# channel_1.net
KiCad netlist of a schematic drawn in Altium Designer
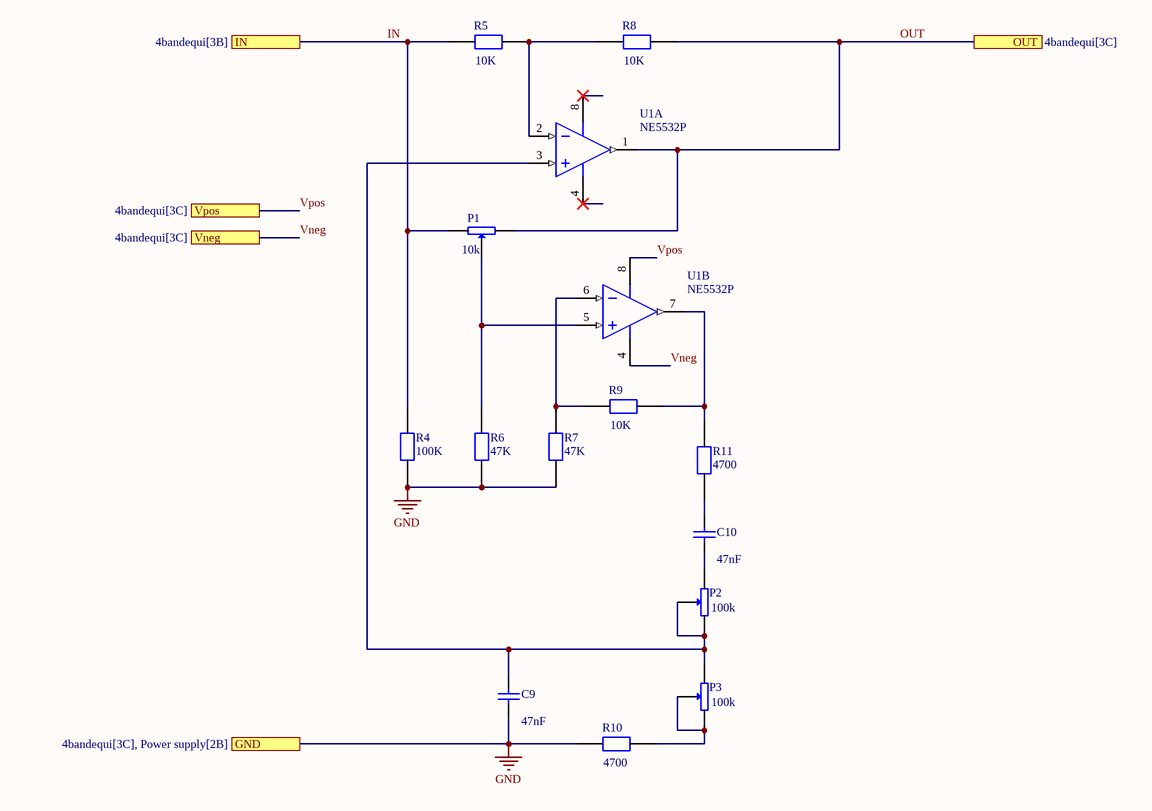
[diagram p0: channel 1.SchDoc]

(export (version "E")
  (design (tool "Eeschema 10.0.6"))
  (components
    (comp (ref "C9")
      (value "47nF")
      (footprint "Capacitor")
      (description "Capacitor")
      (fields (field (name "Comment") "Cap") (field (name "PUBLISHER") "Altium Limited"))
      (libsource (lib "Miscellaneous Devices") (part "Cap"))
    )
    (comp (ref "C10")
      (value "47nF")
      (footprint "Capacitor")
      (description "Capacitor")
      (fields (field (name "Comment") "Cap") (field (name "PUBLISHER") "Altium Limited"))
      (libsource (lib "Miscellaneous Devices") (part "Cap"))
    )
    (comp (ref "P1")
      (value "10k")
      (footprint "header 3")
      (fields (field (name "Comment") "potentiometer"))
      (libsource (lib "4bandequi") (part "potentiometer"))
    )
    (comp (ref "P2")
      (value "100k")
      (footprint "header 3")
      (fields (field (name "Comment") "potentiometer"))
      (libsource (lib "4bandequi") (part "potentiometer"))
    )
    (comp (ref "P3")
      (value "100k")
      (footprint "header 3")
      (fields (field (name "Comment") "potentiometer"))
      (libsource (lib "4bandequi") (part "potentiometer"))
    )
    (comp (ref "R4")
      (value "100K")
      (footprint "resistor")
      (description "resistor")
      (fields (field (name "Comment") "Resistor_Axial"))
      (libsource (lib "4bandequi") (part "Resistor_Axial"))
    )
    (comp (ref "R5")
      (value "10K")
      (footprint "resistor")
      (description "resistor")
      (fields (field (name "Comment") "Resistor_Axial"))
      (libsource (lib "4bandequi") (part "Resistor_Axial"))
    )
    (comp (ref "R6")
      (value "47K")
      (footprint "resistor")
      (description "resistor")
      (fields (field (name "Comment") "Resistor_Axial"))
      (libsource (lib "4bandequi") (part "Resistor_Axial"))
    )
    (comp (ref "R7")
      (value "47K")
      (footprint "resistor")
      (description "resistor")
      (fields (field (name "Comment") "Resistor_Axial"))
      (libsource (lib "4bandequi") (part "Resistor_Axial"))
    )
    (comp (ref "R8")
      (value "10K")
      (footprint "resistor")
      (description "resistor")
      (fields (field (name "Comment") "Resistor_Axial"))
      (libsource (lib "4bandequi") (part "Resistor_Axial"))
    )
    (comp (ref "R9")
      (value "10K")
      (footprint "resistor")
      (description "resistor")
      (fields (field (name "Comment") "Resistor_Axial"))
      (libsource (lib "4bandequi") (part "Resistor_Axial"))
    )
    (comp (ref "R10")
      (value "4700")
      (footprint "resistor")
      (description "resistor")
      (fields (field (name "Comment") "Resistor_Axial"))
      (libsource (lib "4bandequi") (part "Resistor_Axial"))
    )
    (comp (ref "R11")
      (value "4700")
      (footprint "resistor")
      (description "resistor")
      (fields (field (name "Comment") "Resistor_Axial"))
      (libsource (lib "4bandequi") (part "Resistor_Axial"))
    )
    (comp (ref "U1")
      (value "NE5532P")
      (footprint "opamp")
      (fields (field (name "MANUFACTURER") "Texas Instruments"))
      (libsource (lib "4bandequi") (part "CMP-0017-00910-2"))
    )
  )
  (nets
    (net (code "1") (name "/IN") (class "Default")
      (node (ref "P1") (pin "3") (pinfunction "3_3") (pintype "passive"))
      (node (ref "R4") (pin "2") (pinfunction "2_2") (pintype "passive"))
      (node (ref "R5") (pin "1") (pinfunction "1_1") (pintype "passive"))
    )
    (net (code "2") (name "/OUT") (class "Default")
      (node (ref "P1") (pin "1") (pinfunction "1_1") (pintype "passive"))
      (node (ref "R8") (pin "2") (pinfunction "2_2") (pintype "passive"))
      (node (ref "U1") (pin "1") (pinfunction "OUT1_1") (pintype "output"))
    )
    (net (code "3") (name "/Vneg") (class "Default")
      (node (ref "U1") (pin "4") (pinfunction "VCC-_4") (pintype "power_in"))
    )
    (net (code "4") (name "/Vpos") (class "Default")
      (node (ref "U1") (pin "8") (pinfunction "VCC+_8") (pintype "power_in"))
    )
    (net (code "5") (name "GND") (class "Default")
      (node (ref "C9") (pin "1") (pinfunction "1_1") (pintype "passive"))
      (node (ref "R10") (pin "1") (pinfunction "1_1") (pintype "passive"))
      (node (ref "R4") (pin "1") (pinfunction "1_1") (pintype "passive"))
      (node (ref "R6") (pin "2") (pinfunction "2_2") (pintype "passive"))
      (node (ref "R7") (pin "1") (pinfunction "1_1") (pintype "passive"))
    )
    (net (code "6") (name "Net-(C10-Pad1)") (class "Default")
      (node (ref "C10") (pin "1") (pinfunction "1_1") (pintype "passive"))
      (node (ref "P2") (pin "3") (pinfunction "3_3") (pintype "passive"))
    )
    (net (code "7") (name "Net-(C10-Pad2)") (class "Default")
      (node (ref "C10") (pin "2") (pinfunction "2_2") (pintype "passive"))
      (node (ref "R11") (pin "1") (pinfunction "1_1") (pintype "passive"))
    )
    (net (code "8") (name "Net-(P3-Pad1)") (class "Default")
      (node (ref "P3") (pin "1") (pinfunction "1_1") (pintype "passive"))
      (node (ref "P3") (pin "2") (pinfunction "2_2") (pintype "passive"))
      (node (ref "R10") (pin "2") (pinfunction "2_2") (pintype "passive"))
    )
    (net (code "9") (name "Net-(U1A-IN1+)") (class "Default")
      (node (ref "C9") (pin "2") (pinfunction "2_2") (pintype "passive"))
      (node (ref "P2") (pin "1") (pinfunction "1_1") (pintype "passive"))
      (node (ref "P2") (pin "2") (pinfunction "2_2") (pintype "passive"))
      (node (ref "P3") (pin "3") (pinfunction "3_3") (pintype "passive"))
      (node (ref "U1") (pin "3") (pinfunction "IN1+_3") (pintype "input"))
    )
    (net (code "10") (name "Net-(U1A-IN1-)") (class "Default")
      (node (ref "R5") (pin "2") (pinfunction "2_2") (pintype "passive"))
      (node (ref "R8") (pin "1") (pinfunction "1_1") (pintype "passive"))
      (node (ref "U1") (pin "2") (pinfunction "IN1-_2") (pintype "input"))
    )
    (net (code "11") (name "Net-(U1B-IN2+)") (class "Default")
      (node (ref "P1") (pin "2") (pinfunction "2_2") (pintype "passive"))
      (node (ref "R6") (pin "1") (pinfunction "1_1") (pintype "passive"))
      (node (ref "U1") (pin "5") (pinfunction "IN2+_5") (pintype "input"))
    )
    (net (code "12") (name "Net-(U1B-IN2-)") (class "Default")
      (node (ref "R7") (pin "2") (pinfunction "2_2") (pintype "passive"))
      (node (ref "R9") (pin "1") (pinfunction "1_1") (pintype "passive"))
      (node (ref "U1") (pin "6") (pinfunction "IN2-_6") (pintype "input"))
    )
    (net (code "13") (name "Net-(U1B-OUT2)") (class "Default")
      (node (ref "R11") (pin "2") (pinfunction "2_2") (pintype "passive"))
      (node (ref "R9") (pin "2") (pinfunction "2_2") (pintype "passive"))
      (node (ref "U1") (pin "7") (pinfunction "OUT2_7") (pintype "output"))
    )
    (net (code "14") (name "unconnected-(U1A-VCC+-Pad8)") (class "Default")
      (node (ref "U1") (pin "8") (pinfunction "VCC+_8") (pintype "power_in+no_connect"))
    )
    (net (code "15") (name "unconnected-(U1A-VCC--Pad4)") (class "Default")
      (node (ref "U1") (pin "4") (pinfunction "VCC-_4") (pintype "power_in+no_connect"))
    )
  )
)
